# PCB-VU-SE-1.net
KiCad netlist of a schematic drawn in EAGLE
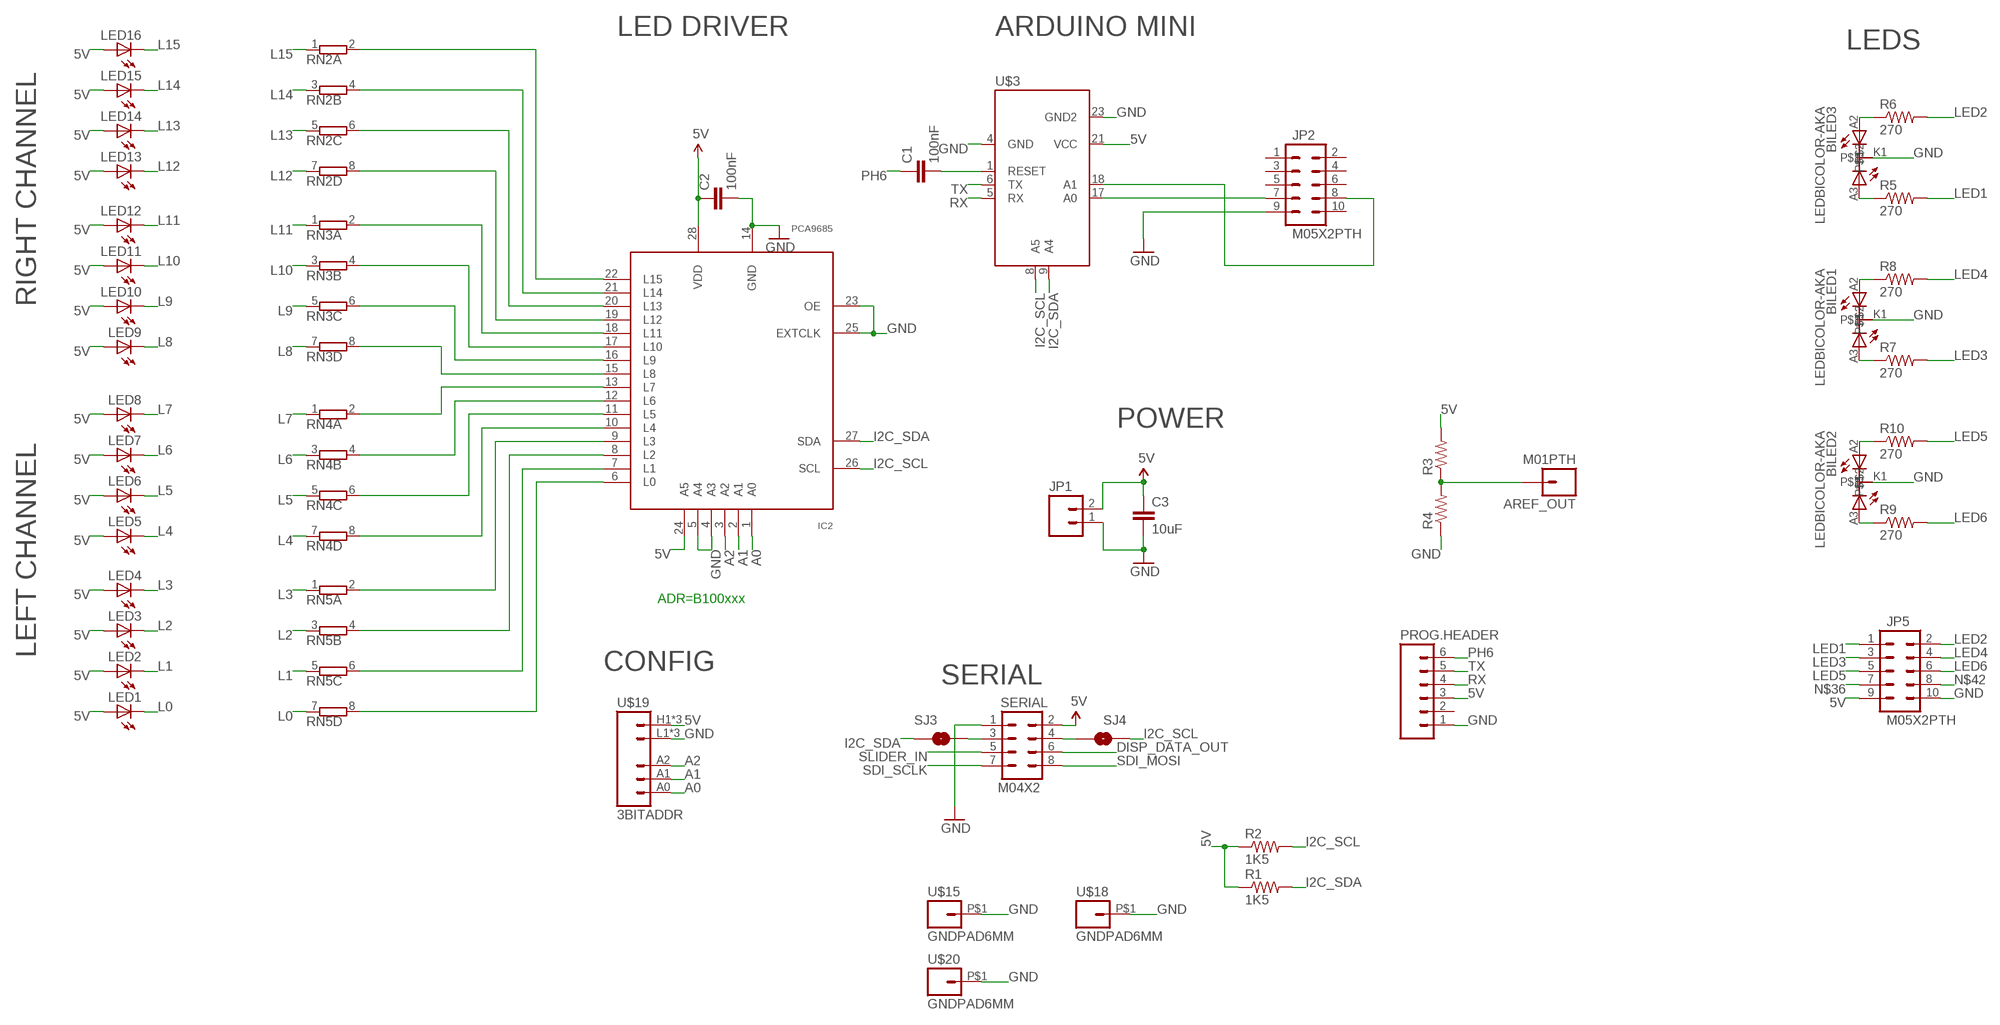
[diagram p0: schematic, sheet 1]

(export (version "E")
  (design (tool "Eeschema 10.0.6"))
  (components
    (comp (ref "AREF_OUT")
      (value "M01PTH")
      (footprint "eagle-import:1X01")
      (libsource (lib "eagle-import") (part "M01PTH"))
    )
    (comp (ref "BILED1")
      (value "LEDBICOLOR-AKA")
      (footprint "eagle-import:LED5MM-BICOLOR")
      (libsource (lib "eagle-import") (part "LEDBICOLOR-AKA"))
    )
    (comp (ref "BILED2")
      (value "LEDBICOLOR-AKA")
      (footprint "eagle-import:LED5MM-BICOLOR")
      (libsource (lib "eagle-import") (part "LEDBICOLOR-AKA"))
    )
    (comp (ref "BILED3")
      (value "LEDBICOLOR-AKA")
      (footprint "eagle-import:LED5MM-BICOLOR")
      (libsource (lib "eagle-import") (part "LEDBICOLOR-AKA"))
    )
    (comp (ref "C1")
      (value "100nF")
      (footprint "eagle-import:0603-CAP")
      (libsource (lib "eagle-import") (part "CAP0603-CAP"))
    )
    (comp (ref "C2")
      (value "100nF")
      (footprint "eagle-import:0603-CAP")
      (libsource (lib "eagle-import") (part "CAP0603-CAP"))
    )
    (comp (ref "C3")
      (value "10uF")
      (footprint "eagle-import:0805")
      (libsource (lib "eagle-import") (part "CAP0805"))
    )
    (comp (ref "IC2")
      (value "PCA9685")
      (footprint "eagle-import:TSSOP28")
      (libsource (lib "eagle-import") (part "PCA9685"))
    )
    (comp (ref "JP1")
      (value "M02PTH")
      (footprint "eagle-import:1X02")
      (libsource (lib "eagle-import") (part "M02PTH"))
    )
    (comp (ref "JP2")
      (value "M05X2PTH")
      (footprint "eagle-import:AVR_ICSP")
      (libsource (lib "eagle-import") (part "M05X2PTH"))
    )
    (comp (ref "JP5")
      (value "M05X2PTH")
      (footprint "eagle-import:AVR_ICSP")
      (libsource (lib "eagle-import") (part "M05X2PTH"))
    )
    (comp (ref "LED1")
      (value "LED3MM")
      (footprint "eagle-import:LED3MM")
      (libsource (lib "eagle-import") (part "LED3MM"))
    )
    (comp (ref "LED2")
      (value "LED3MM")
      (footprint "eagle-import:LED3MM")
      (libsource (lib "eagle-import") (part "LED3MM"))
    )
    (comp (ref "LED3")
      (value "LED3MM")
      (footprint "eagle-import:LED3MM")
      (libsource (lib "eagle-import") (part "LED3MM"))
    )
    (comp (ref "LED4")
      (value "LED3MM")
      (footprint "eagle-import:LED3MM")
      (libsource (lib "eagle-import") (part "LED3MM"))
    )
    (comp (ref "LED5")
      (value "LED3MM")
      (footprint "eagle-import:LED3MM")
      (libsource (lib "eagle-import") (part "LED3MM"))
    )
    (comp (ref "LED6")
      (value "LED3MM")
      (footprint "eagle-import:LED3MM")
      (libsource (lib "eagle-import") (part "LED3MM"))
    )
    (comp (ref "LED7")
      (value "LED3MM")
      (footprint "eagle-import:LED3MM")
      (libsource (lib "eagle-import") (part "LED3MM"))
    )
    (comp (ref "LED8")
      (value "LED3MM")
      (footprint "eagle-import:LED3MM")
      (libsource (lib "eagle-import") (part "LED3MM"))
    )
    (comp (ref "LED9")
      (value "LED3MM")
      (footprint "eagle-import:LED3MM")
      (libsource (lib "eagle-import") (part "LED3MM"))
    )
    (comp (ref "LED10")
      (value "LED3MM")
      (footprint "eagle-import:LED3MM")
      (libsource (lib "eagle-import") (part "LED3MM"))
    )
    (comp (ref "LED11")
      (value "LED3MM")
      (footprint "eagle-import:LED3MM")
      (libsource (lib "eagle-import") (part "LED3MM"))
    )
    (comp (ref "LED12")
      (value "LED3MM")
      (footprint "eagle-import:LED3MM")
      (libsource (lib "eagle-import") (part "LED3MM"))
    )
    (comp (ref "LED13")
      (value "LED3MM")
      (footprint "eagle-import:LED3MM")
      (libsource (lib "eagle-import") (part "LED3MM"))
    )
    (comp (ref "LED14")
      (value "LED3MM")
      (footprint "eagle-import:LED3MM")
      (libsource (lib "eagle-import") (part "LED3MM"))
    )
    (comp (ref "LED15")
      (value "LED3MM")
      (footprint "eagle-import:LED3MM")
      (libsource (lib "eagle-import") (part "LED3MM"))
    )
    (comp (ref "LED16")
      (value "LED3MM")
      (footprint "eagle-import:LED3MM")
      (libsource (lib "eagle-import") (part "LED3MM"))
    )
    (comp (ref "PROG.HEADER")
      (value "M06LOCK")
      (footprint "eagle-import:1X06_LOCK")
      (libsource (lib "eagle-import") (part "M06LOCK"))
    )
    (comp (ref "R1")
      (value "1K5")
      (footprint "eagle-import:0603-RES")
      (libsource (lib "eagle-import") (part "RESISTOR0603-RES"))
    )
    (comp (ref "R2")
      (value "1K5")
      (footprint "eagle-import:0603-RES")
      (libsource (lib "eagle-import") (part "RESISTOR0603-RES"))
    )
    (comp (ref "R3")
      (value "RESISTOR0603-RES")
      (footprint "eagle-import:0603-RES")
      (libsource (lib "eagle-import") (part "RESISTOR0603-RES"))
    )
    (comp (ref "R4")
      (value "RESISTOR0603-RES")
      (footprint "eagle-import:0603-RES")
      (libsource (lib "eagle-import") (part "RESISTOR0603-RES"))
    )
    (comp (ref "R5")
      (value "270")
      (footprint "eagle-import:0603-RES")
      (libsource (lib "eagle-import") (part "RESISTOR0603-RES"))
    )
    (comp (ref "R6")
      (value "270")
      (footprint "eagle-import:0603-RES")
      (libsource (lib "eagle-import") (part "RESISTOR0603-RES"))
    )
    (comp (ref "R7")
      (value "270")
      (footprint "eagle-import:0603-RES")
      (libsource (lib "eagle-import") (part "RESISTOR0603-RES"))
    )
    (comp (ref "R8")
      (value "270")
      (footprint "eagle-import:0603-RES")
      (libsource (lib "eagle-import") (part "RESISTOR0603-RES"))
    )
    (comp (ref "R9")
      (value "270")
      (footprint "eagle-import:0603-RES")
      (libsource (lib "eagle-import") (part "RESISTOR0603-RES"))
    )
    (comp (ref "R10")
      (value "270")
      (footprint "eagle-import:0603-RES")
      (libsource (lib "eagle-import") (part "RESISTOR0603-RES"))
    )
    (comp (ref "RN2")
      (value "E4R")
      (footprint "eagle-import:SIL8")
      (libsource (lib "eagle-import") (part "E4R"))
    )
    (comp (ref "RN3")
      (value "E4R")
      (footprint "eagle-import:SIL8")
      (libsource (lib "eagle-import") (part "E4R"))
    )
    (comp (ref "RN4")
      (value "E4R")
      (footprint "eagle-import:SIL8")
      (libsource (lib "eagle-import") (part "E4R"))
    )
    (comp (ref "RN5")
      (value "E4R")
      (footprint "eagle-import:SIL8")
      (libsource (lib "eagle-import") (part "E4R"))
    )
    (comp (ref "SERIAL")
      (value "M04X2")
      (footprint "eagle-import:2X4")
      (libsource (lib "eagle-import") (part "M04X2"))
    )
    (comp (ref "SJ3")
      (value "SOLDERJUMPERNC")
      (footprint "eagle-import:SJ_2S")
      (libsource (lib "eagle-import") (part "SOLDERJUMPERNC"))
    )
    (comp (ref "SJ4")
      (value "SOLDERJUMPERNC")
      (footprint "eagle-import:SJ_2S")
      (libsource (lib "eagle-import") (part "SOLDERJUMPERNC"))
    )
    (comp (ref "U$3")
      (value "ARDUINO_MINI_SE1")
      (footprint "eagle-import:ARDUINO_MINI_SE1")
      (libsource (lib "eagle-import") (part "ARDUINO_MINI_SE1"))
    )
    (comp (ref "U$15")
      (value "GNDPAD6MM")
      (footprint "eagle-import:3.2MMPAD6MM")
      (libsource (lib "eagle-import") (part "GNDPAD6MM"))
    )
    (comp (ref "U$18")
      (value "GNDPAD6MM")
      (footprint "eagle-import:3.2MMPAD6MM")
      (libsource (lib "eagle-import") (part "GNDPAD6MM"))
    )
    (comp (ref "U$19")
      (value "3BITADDR")
      (footprint "eagle-import:3BITADDR")
      (libsource (lib "eagle-import") (part "3BITADDR"))
    )
    (comp (ref "U$20")
      (value "GNDPAD6MM")
      (footprint "eagle-import:3.2MMPAD6MM")
      (libsource (lib "eagle-import") (part "GNDPAD6MM"))
    )
  )
  (nets
    (net (code "1") (name "/A0") (class "Default")
      (node (ref "IC2") (pin "1") (pinfunction "A0_1") (pintype "input"))
      (node (ref "U$19") (pin "A0") (pinfunction "A0_A0") (pintype "passive"))
    )
    (net (code "2") (name "/A1") (class "Default")
      (node (ref "IC2") (pin "2") (pinfunction "A1_2") (pintype "input"))
      (node (ref "U$19") (pin "A1") (pinfunction "A1_A1") (pintype "passive"))
    )
    (net (code "3") (name "/A2") (class "Default")
      (node (ref "IC2") (pin "3") (pinfunction "A2_3") (pintype "input"))
      (node (ref "U$19") (pin "A2") (pinfunction "A2_A2") (pintype "passive"))
    )
    (net (code "4") (name "/DISP_DATA_OUT") (class "Default")
      (node (ref "SERIAL") (pin "6") (pinfunction "6_6") (pintype "passive"))
    )
    (net (code "5") (name "/I2C_SCL") (class "Default")
      (node (ref "IC2") (pin "26") (pinfunction "SCL_26") (pintype "input"))
      (node (ref "R2") (pin "2") (pinfunction "2_2") (pintype "passive"))
      (node (ref "SJ4") (pin "2") (pinfunction "2_2") (pintype "passive"))
      (node (ref "U$3") (pin "8") (pinfunction "A5_8") (pintype "bidirectional"))
    )
    (net (code "6") (name "/I2C_SDA") (class "Default")
      (node (ref "IC2") (pin "27") (pinfunction "SDA_27") (pintype "input"))
      (node (ref "R1") (pin "2") (pinfunction "2_2") (pintype "passive"))
      (node (ref "SJ3") (pin "1") (pinfunction "1_1") (pintype "passive"))
      (node (ref "U$3") (pin "9") (pinfunction "A4_9") (pintype "bidirectional"))
    )
    (net (code "7") (name "/L0") (class "Default")
      (node (ref "LED1") (pin "K") (pinfunction "C_K") (pintype "passive"))
      (node (ref "RN5") (pin "7") (pinfunction "1_7") (pintype "passive"))
    )
    (net (code "8") (name "/L1") (class "Default")
      (node (ref "LED2") (pin "K") (pinfunction "C_K") (pintype "passive"))
      (node (ref "RN5") (pin "5") (pinfunction "1_5") (pintype "passive"))
    )
    (net (code "9") (name "/L2") (class "Default")
      (node (ref "LED3") (pin "K") (pinfunction "C_K") (pintype "passive"))
      (node (ref "RN5") (pin "3") (pinfunction "1_3") (pintype "passive"))
    )
    (net (code "10") (name "/L3") (class "Default")
      (node (ref "LED4") (pin "K") (pinfunction "C_K") (pintype "passive"))
      (node (ref "RN5") (pin "1") (pinfunction "1_1") (pintype "passive"))
    )
    (net (code "11") (name "/L4") (class "Default")
      (node (ref "LED5") (pin "K") (pinfunction "C_K") (pintype "passive"))
      (node (ref "RN4") (pin "7") (pinfunction "1_7") (pintype "passive"))
    )
    (net (code "12") (name "/L5") (class "Default")
      (node (ref "LED6") (pin "K") (pinfunction "C_K") (pintype "passive"))
      (node (ref "RN4") (pin "5") (pinfunction "1_5") (pintype "passive"))
    )
    (net (code "13") (name "/L6") (class "Default")
      (node (ref "LED7") (pin "K") (pinfunction "C_K") (pintype "passive"))
      (node (ref "RN4") (pin "3") (pinfunction "1_3") (pintype "passive"))
    )
    (net (code "14") (name "/L7") (class "Default")
      (node (ref "LED8") (pin "K") (pinfunction "C_K") (pintype "passive"))
      (node (ref "RN4") (pin "1") (pinfunction "1_1") (pintype "passive"))
    )
    (net (code "15") (name "/L8") (class "Default")
      (node (ref "LED9") (pin "K") (pinfunction "C_K") (pintype "passive"))
      (node (ref "RN3") (pin "7") (pinfunction "1_7") (pintype "passive"))
    )
    (net (code "16") (name "/L9") (class "Default")
      (node (ref "LED10") (pin "K") (pinfunction "C_K") (pintype "passive"))
      (node (ref "RN3") (pin "5") (pinfunction "1_5") (pintype "passive"))
    )
    (net (code "17") (name "/L10") (class "Default")
      (node (ref "LED11") (pin "K") (pinfunction "C_K") (pintype "passive"))
      (node (ref "RN3") (pin "3") (pinfunction "1_3") (pintype "passive"))
    )
    (net (code "18") (name "/L11") (class "Default")
      (node (ref "LED12") (pin "K") (pinfunction "C_K") (pintype "passive"))
      (node (ref "RN3") (pin "1") (pinfunction "1_1") (pintype "passive"))
    )
    (net (code "19") (name "/L12") (class "Default")
      (node (ref "LED13") (pin "K") (pinfunction "C_K") (pintype "passive"))
      (node (ref "RN2") (pin "7") (pinfunction "1_7") (pintype "passive"))
    )
    (net (code "20") (name "/L13") (class "Default")
      (node (ref "LED14") (pin "K") (pinfunction "C_K") (pintype "passive"))
      (node (ref "RN2") (pin "5") (pinfunction "1_5") (pintype "passive"))
    )
    (net (code "21") (name "/L14") (class "Default")
      (node (ref "LED15") (pin "K") (pinfunction "C_K") (pintype "passive"))
      (node (ref "RN2") (pin "3") (pinfunction "1_3") (pintype "passive"))
    )
    (net (code "22") (name "/L15") (class "Default")
      (node (ref "LED16") (pin "K") (pinfunction "C_K") (pintype "passive"))
      (node (ref "RN2") (pin "1") (pinfunction "1_1") (pintype "passive"))
    )
    (net (code "23") (name "/LED1") (class "Default")
      (node (ref "JP5") (pin "1") (pinfunction "1_1") (pintype "passive"))
      (node (ref "R5") (pin "2") (pinfunction "2_2") (pintype "passive"))
    )
    (net (code "24") (name "/LED2") (class "Default")
      (node (ref "JP5") (pin "2") (pinfunction "2_2") (pintype "passive"))
      (node (ref "R6") (pin "2") (pinfunction "2_2") (pintype "passive"))
    )
    (net (code "25") (name "/LED3") (class "Default")
      (node (ref "JP5") (pin "3") (pinfunction "3_3") (pintype "passive"))
      (node (ref "R7") (pin "2") (pinfunction "2_2") (pintype "passive"))
    )
    (net (code "26") (name "/LED4") (class "Default")
      (node (ref "JP5") (pin "4") (pinfunction "4_4") (pintype "passive"))
      (node (ref "R8") (pin "2") (pinfunction "2_2") (pintype "passive"))
    )
    (net (code "27") (name "/LED5") (class "Default")
      (node (ref "JP5") (pin "5") (pinfunction "5_5") (pintype "passive"))
      (node (ref "R10") (pin "2") (pinfunction "2_2") (pintype "passive"))
    )
    (net (code "28") (name "/LED6") (class "Default")
      (node (ref "JP5") (pin "6") (pinfunction "6_6") (pintype "passive"))
      (node (ref "R9") (pin "2") (pinfunction "2_2") (pintype "passive"))
    )
    (net (code "29") (name "/N$36") (class "Default")
      (node (ref "JP5") (pin "7") (pinfunction "7_7") (pintype "passive"))
    )
    (net (code "30") (name "/N$42") (class "Default")
      (node (ref "JP5") (pin "8") (pinfunction "8_8") (pintype "passive"))
    )
    (net (code "31") (name "/PH6") (class "Default")
      (node (ref "C1") (pin "1") (pinfunction "1_1") (pintype "passive"))
      (node (ref "PROG.HEADER") (pin "6") (pinfunction "6_6") (pintype "passive"))
    )
    (net (code "32") (name "/RX") (class "Default")
      (node (ref "PROG.HEADER") (pin "4") (pinfunction "4_4") (pintype "passive"))
      (node (ref "U$3") (pin "5") (pinfunction "RX_5") (pintype "bidirectional"))
    )
    (net (code "33") (name "/SDI_MOSI") (class "Default")
      (node (ref "SERIAL") (pin "8") (pinfunction "8_8") (pintype "passive"))
    )
    (net (code "34") (name "/SDI_SCLK") (class "Default")
      (node (ref "SERIAL") (pin "7") (pinfunction "7_7") (pintype "passive"))
    )
    (net (code "35") (name "/SLIDER_IN") (class "Default")
      (node (ref "SERIAL") (pin "5") (pinfunction "5_5") (pintype "passive"))
    )
    (net (code "36") (name "/TX") (class "Default")
      (node (ref "PROG.HEADER") (pin "5") (pinfunction "5_5") (pintype "passive"))
      (node (ref "U$3") (pin "6") (pinfunction "TX_6") (pintype "bidirectional"))
    )
    (net (code "37") (name "5V") (class "Default")
      (node (ref "C2") (pin "1") (pinfunction "1_1") (pintype "passive"))
      (node (ref "C3") (pin "1") (pinfunction "1_1") (pintype "passive"))
      (node (ref "IC2") (pin "24") (pinfunction "A5_24") (pintype "input"))
      (node (ref "IC2") (pin "28") (pinfunction "VDD_28") (pintype "power_in"))
      (node (ref "JP1") (pin "2") (pinfunction "2_2") (pintype "passive"))
      (node (ref "JP5") (pin "9") (pinfunction "9_9") (pintype "passive"))
      (node (ref "LED1") (pin "A") (pinfunction "A_A") (pintype "passive"))
      (node (ref "LED10") (pin "A") (pinfunction "A_A") (pintype "passive"))
      (node (ref "LED11") (pin "A") (pinfunction "A_A") (pintype "passive"))
      (node (ref "LED12") (pin "A") (pinfunction "A_A") (pintype "passive"))
      (node (ref "LED13") (pin "A") (pinfunction "A_A") (pintype "passive"))
      (node (ref "LED14") (pin "A") (pinfunction "A_A") (pintype "passive"))
      (node (ref "LED15") (pin "A") (pinfunction "A_A") (pintype "passive"))
      (node (ref "LED16") (pin "A") (pinfunction "A_A") (pintype "passive"))
      (node (ref "LED2") (pin "A") (pinfunction "A_A") (pintype "passive"))
      (node (ref "LED3") (pin "A") (pinfunction "A_A") (pintype "passive"))
      (node (ref "LED4") (pin "A") (pinfunction "A_A") (pintype "passive"))
      (node (ref "LED5") (pin "A") (pinfunction "A_A") (pintype "passive"))
      (node (ref "LED6") (pin "A") (pinfunction "A_A") (pintype "passive"))
      (node (ref "LED7") (pin "A") (pinfunction "A_A") (pintype "passive"))
      (node (ref "LED8") (pin "A") (pinfunction "A_A") (pintype "passive"))
      (node (ref "LED9") (pin "A") (pinfunction "A_A") (pintype "passive"))
      (node (ref "PROG.HEADER") (pin "3") (pinfunction "3_3") (pintype "passive"))
      (node (ref "R1") (pin "1") (pinfunction "1_1") (pintype "passive"))
      (node (ref "R2") (pin "1") (pinfunction "1_1") (pintype "passive"))
      (node (ref "R3") (pin "2") (pinfunction "2_2") (pintype "passive"))
      (node (ref "SERIAL") (pin "2") (pinfunction "2_2") (pintype "passive"))
      (node (ref "U$19") (pin "H1") (pinfunction "VCC_H1") (pintype "passive"))
      (node (ref "U$19") (pin "H2") (pinfunction "VCC_H2") (pintype "passive"))
      (node (ref "U$19") (pin "H3") (pinfunction "VCC_H3") (pintype "passive"))
      (node (ref "U$3") (pin "21") (pinfunction "VCC_21") (pintype "bidirectional"))
    )
    (net (code "38") (name "GND") (class "Default")
      (node (ref "BILED1") (pin "K1") (pinfunction "P$1_K1") (pintype "bidirectional"))
      (node (ref "BILED2") (pin "K1") (pinfunction "P$1_K1") (pintype "bidirectional"))
      (node (ref "BILED3") (pin "K1") (pinfunction "P$1_K1") (pintype "bidirectional"))
      (node (ref "C2") (pin "2") (pinfunction "2_2") (pintype "passive"))
      (node (ref "C3") (pin "2") (pinfunction "2_2") (pintype "passive"))
      (node (ref "IC2") (pin "14") (pinfunction "GND_14") (pintype "power_in"))
      (node (ref "IC2") (pin "23") (pinfunction "OE_23") (pintype "input"))
      (node (ref "IC2") (pin "25") (pinfunction "EXTCLK_25") (pintype "input"))
      (node (ref "IC2") (pin "4") (pinfunction "A3_4") (pintype "input"))
      (node (ref "IC2") (pin "5") (pinfunction "A4_5") (pintype "input"))
      (node (ref "JP1") (pin "1") (pinfunction "1_1") (pintype "passive"))
      (node (ref "JP2") (pin "9") (pinfunction "9_9") (pintype "passive"))
      (node (ref "JP5") (pin "10") (pinfunction "10_10") (pintype "passive"))
      (node (ref "PROG.HEADER") (pin "1") (pinfunction "1_1") (pintype "passive"))
      (node (ref "R4") (pin "1") (pinfunction "1_1") (pintype "passive"))
      (node (ref "SERIAL") (pin "1") (pinfunction "1_1") (pintype "passive"))
      (node (ref "U$15") (pin "P$1") (pinfunction "1_P$1") (pintype "passive"))
      (node (ref "U$18") (pin "P$1") (pinfunction "1_P$1") (pintype "passive"))
      (node (ref "U$19") (pin "L1") (pinfunction "GND_L1") (pintype "passive"))
      (node (ref "U$19") (pin "L2") (pinfunction "GND_L2") (pintype "passive"))
      (node (ref "U$19") (pin "L3") (pinfunction "GND_L3") (pintype "passive"))
      (node (ref "U$20") (pin "P$1") (pinfunction "1_P$1") (pintype "passive"))
      (node (ref "U$3") (pin "23") (pinfunction "GND2_23") (pintype "bidirectional"))
      (node (ref "U$3") (pin "4") (pinfunction "GND_4") (pintype "bidirectional"))
    )
    (net (code "39") (name "Net-(AREF_OUT-Pad1)") (class "Default")
      (node (ref "AREF_OUT") (pin "1") (pinfunction "1_1") (pintype "passive"))
      (node (ref "R3") (pin "1") (pinfunction "1_1") (pintype "passive"))
      (node (ref "R4") (pin "2") (pinfunction "2_2") (pintype "passive"))
    )
    (net (code "40") (name "Net-(BILED1-P$2)") (class "Default")
      (node (ref "BILED1") (pin "A2") (pinfunction "P$2_A2") (pintype "bidirectional"))
      (node (ref "R8") (pin "1") (pinfunction "1_1") (pintype "passive"))
    )
    (net (code "41") (name "Net-(BILED1-P$3)") (class "Default")
      (node (ref "BILED1") (pin "A3") (pinfunction "P$3_A3") (pintype "bidirectional"))
      (node (ref "R7") (pin "1") (pinfunction "1_1") (pintype "passive"))
    )
    (net (code "42") (name "Net-(BILED2-P$2)") (class "Default")
      (node (ref "BILED2") (pin "A2") (pinfunction "P$2_A2") (pintype "bidirectional"))
      (node (ref "R10") (pin "1") (pinfunction "1_1") (pintype "passive"))
    )
    (net (code "43") (name "Net-(BILED2-P$3)") (class "Default")
      (node (ref "BILED2") (pin "A3") (pinfunction "P$3_A3") (pintype "bidirectional"))
      (node (ref "R9") (pin "1") (pinfunction "1_1") (pintype "passive"))
    )
    (net (code "44") (name "Net-(BILED3-P$2)") (class "Default")
      (node (ref "BILED3") (pin "A2") (pinfunction "P$2_A2") (pintype "bidirectional"))
      (node (ref "R6") (pin "1") (pinfunction "1_1") (pintype "passive"))
    )
    (net (code "45") (name "Net-(BILED3-P$3)") (class "Default")
      (node (ref "BILED3") (pin "A3") (pinfunction "P$3_A3") (pintype "bidirectional"))
      (node (ref "R5") (pin "1") (pinfunction "1_1") (pintype "passive"))
    )
    (net (code "46") (name "Net-(IC2-L0)") (class "Default")
      (node (ref "IC2") (pin "6") (pinfunction "L0_6") (pintype "output"))
      (node (ref "RN5") (pin "8") (pinfunction "2_8") (pintype "passive"))
    )
    (net (code "47") (name "Net-(IC2-L1)") (class "Default")
      (node (ref "IC2") (pin "7") (pinfunction "L1_7") (pintype "output"))
      (node (ref "RN5") (pin "6") (pinfunction "2_6") (pintype "passive"))
    )
    (net (code "48") (name "Net-(IC2-L2)") (class "Default")
      (node (ref "IC2") (pin "8") (pinfunction "L2_8") (pintype "output"))
      (node (ref "RN5") (pin "4") (pinfunction "2_4") (pintype "passive"))
    )
    (net (code "49") (name "Net-(IC2-L3)") (class "Default")
      (node (ref "IC2") (pin "9") (pinfunction "L3_9") (pintype "output"))
      (node (ref "RN5") (pin "2") (pinfunction "2_2") (pintype "passive"))
    )
    (net (code "50") (name "Net-(IC2-L4)") (class "Default")
      (node (ref "IC2") (pin "10") (pinfunction "L4_10") (pintype "output"))
      (node (ref "RN4") (pin "8") (pinfunction "2_8") (pintype "passive"))
    )
    (net (code "51") (name "Net-(IC2-L5)") (class "Default")
      (node (ref "IC2") (pin "11") (pinfunction "L5_11") (pintype "output"))
      (node (ref "RN4") (pin "6") (pinfunction "2_6") (pintype "passive"))
    )
    (net (code "52") (name "Net-(IC2-L6)") (class "Default")
      (node (ref "IC2") (pin "12") (pinfunction "L6_12") (pintype "output"))
      (node (ref "RN4") (pin "4") (pinfunction "2_4") (pintype "passive"))
    )
    (net (code "53") (name "Net-(IC2-L7)") (class "Default")
      (node (ref "IC2") (pin "13") (pinfunction "L7_13") (pintype "output"))
      (node (ref "RN4") (pin "2") (pinfunction "2_2") (pintype "passive"))
    )
    (net (code "54") (name "Net-(IC2-L8)") (class "Default")
      (node (ref "IC2") (pin "15") (pinfunction "L8_15") (pintype "output"))
      (node (ref "RN3") (pin "8") (pinfunction "2_8") (pintype "passive"))
    )
    (net (code "55") (name "Net-(IC2-L9)") (class "Default")
      (node (ref "IC2") (pin "16") (pinfunction "L9_16") (pintype "output"))
      (node (ref "RN3") (pin "6") (pinfunction "2_6") (pintype "passive"))
    )
    (net (code "56") (name "Net-(IC2-L10)") (class "Default")
      (node (ref "IC2") (pin "17") (pinfunction "L10_17") (pintype "output"))
      (node (ref "RN3") (pin "4") (pinfunction "2_4") (pintype "passive"))
    )
    (net (code "57") (name "Net-(IC2-L11)") (class "Default")
      (node (ref "IC2") (pin "18") (pinfunction "L11_18") (pintype "output"))
      (node (ref "RN3") (pin "2") (pinfunction "2_2") (pintype "passive"))
    )
    (net (code "58") (name "Net-(IC2-L12)") (class "Default")
      (node (ref "IC2") (pin "19") (pinfunction "L12_19") (pintype "output"))
      (node (ref "RN2") (pin "8") (pinfunction "2_8") (pintype "passive"))
    )
    (net (code "59") (name "Net-(IC2-L13)") (class "Default")
      (node (ref "IC2") (pin "20") (pinfunction "L13_20") (pintype "output"))
      (node (ref "RN2") (pin "6") (pinfunction "2_6") (pintype "passive"))
    )
    (net (code "60") (name "Net-(IC2-L14)") (class "Default")
      (node (ref "IC2") (pin "21") (pinfunction "L14_21") (pintype "output"))
      (node (ref "RN2") (pin "4") (pinfunction "2_4") (pintype "passive"))
    )
    (net (code "61") (name "Net-(IC2-L15)") (class "Default")
      (node (ref "IC2") (pin "22") (pinfunction "L15_22") (pintype "output"))
      (node (ref "RN2") (pin "2") (pinfunction "2_2") (pintype "passive"))
    )
    (net (code "62") (name "Net-(SERIAL-Pad3)") (class "Default")
      (node (ref "SERIAL") (pin "3") (pinfunction "3_3") (pintype "passive"))
      (node (ref "SJ3") (pin "2") (pinfunction "2_2") (pintype "passive"))
    )
    (net (code "63") (name "Net-(SERIAL-Pad4)") (class "Default")
      (node (ref "SERIAL") (pin "4") (pinfunction "4_4") (pintype "passive"))
      (node (ref "SJ4") (pin "1") (pinfunction "1_1") (pintype "passive"))
    )
    (net (code "64") (name "Net-(U$3-A0)") (class "Default")
      (node (ref "JP2") (pin "7") (pinfunction "7_7") (pintype "passive"))
      (node (ref "U$3") (pin "17") (pinfunction "A0_17") (pintype "bidirectional"))
    )
    (net (code "65") (name "Net-(U$3-A1)") (class "Default")
      (node (ref "JP2") (pin "8") (pinfunction "8_8") (pintype "passive"))
      (node (ref "U$3") (pin "18") (pinfunction "A1_18") (pintype "bidirectional"))
    )
    (net (code "66") (name "Net-(U$3-RESET)") (class "Default")
      (node (ref "C1") (pin "2") (pinfunction "2_2") (pintype "passive"))
      (node (ref "U$3") (pin "1") (pinfunction "RESET_1") (pintype "bidirectional"))
    )
    (net (code "67") (name "unconnected-(JP2-Pad1)") (class "Default")
      (node (ref "JP2") (pin "1") (pinfunction "1_1") (pintype "passive"))
    )
    (net (code "68") (name "unconnected-(JP2-Pad2)") (class "Default")
      (node (ref "JP2") (pin "2") (pinfunction "2_2") (pintype "passive"))
    )
    (net (code "69") (name "unconnected-(JP2-Pad3)") (class "Default")
      (node (ref "JP2") (pin "3") (pinfunction "3_3") (pintype "passive"))
    )
    (net (code "70") (name "unconnected-(JP2-Pad4)") (class "Default")
      (node (ref "JP2") (pin "4") (pinfunction "4_4") (pintype "passive"))
    )
    (net (code "71") (name "unconnected-(JP2-Pad5)") (class "Default")
      (node (ref "JP2") (pin "5") (pinfunction "5_5") (pintype "passive"))
    )
    (net (code "72") (name "unconnected-(JP2-Pad6)") (class "Default")
      (node (ref "JP2") (pin "6") (pinfunction "6_6") (pintype "passive"))
    )
    (net (code "73") (name "unconnected-(JP2-Pad10)") (class "Default")
      (node (ref "JP2") (pin "10") (pinfunction "10_10") (pintype "passive"))
    )
    (net (code "74") (name "unconnected-(PROG.HEADER-Pad2)") (class "Default")
      (node (ref "PROG.HEADER") (pin "2") (pinfunction "2_2") (pintype "passive"))
    )
  )
)
